# adc_wing.net
KiCad netlist of a schematic drawn in Altium Designer
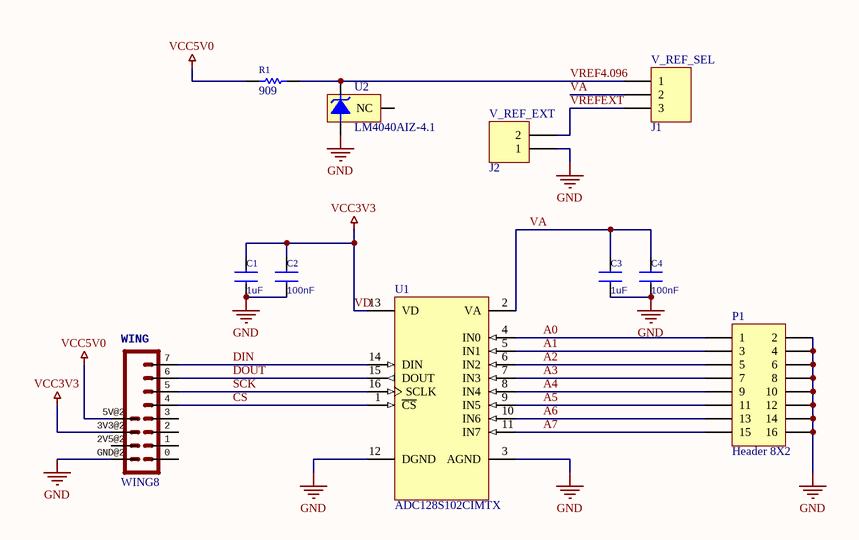
[diagram p0: adc_wing.SchDoc]

(export (version "E")
  (design (tool "Eeschema 10.0.6"))
  (components
    (comp (ref "C1")
      (value "1uF")
      (footprint "C0805")
      (description "Ceramic Capactor size 0805")
      (libsource (lib "MH - RCLDSX") (part "C0805"))
    )
    (comp (ref "C2")
      (value "100nF")
      (footprint "C0603")
      (description "Ceramic Capactor size 0603")
      (libsource (lib "MH - RCLDSX") (part "C0603"))
    )
    (comp (ref "C3")
      (value "1uF")
      (footprint "C0805")
      (description "Ceramic Capactor size 0805")
      (libsource (lib "MH - RCLDSX") (part "C0805"))
    )
    (comp (ref "C4")
      (value "100nF")
      (footprint "C0603")
      (description "Ceramic Capactor size 0603")
      (libsource (lib "MH - RCLDSX") (part "C0603"))
    )
    (comp (ref "J1")
      (value "V_REF_SEL")
      (footprint "PLS-3-3D")
      (description "Header, 3-Pin")
      (fields (field (name "PUBLISHER") "Altium Limited"))
      (libsource (lib "MH - Connectors") (part "PLS-3"))
    )
    (comp (ref "J2")
      (value "V_REF_EXT")
      (footprint "PLS-2-3D")
      (description "Header, 2-Pin")
      (fields (field (name "PUBLISHER") "Altium Limited"))
      (libsource (lib "MH - Connectors") (part "PLS-2"))
    )
    (comp (ref "P1")
      (value "Header 8X2")
      (footprint "HDR2X8")
      (description "Header, 8-Pin, Dual row")
      (fields (field (name "PUBLISHER") "Altium Limited"))
      (libsource (lib "Miscellaneous Connectors") (part "Header 8X2"))
    )
    (comp (ref "R1")
      (value "909")
      (footprint "R0805")
      (description "Chip Resistor size 0805")
      (libsource (lib "MH - RCLDSX") (part "R0805"))
    )
    (comp (ref "U1")
      (value "ADC128S102CIMTX")
      (footprint "MTC16_N")
      (description "8-Channel, 50 kSPS to 200 kSPS, 12-Bit A/D Converter, 16-pin TSSOP")
      (fields
        (field (name "PARTNUMBER") "ADC128S022CIMTX")
        (field (name "MANUFACTURER") "National Semiconductor")
      )
      (libsource (lib "National Semiconductor ADC") (part "ADC128S022CIMTX"))
    )
    (comp (ref "U2")
      (value "LM4040AIZ-4.1")
      (footprint "Z03A")
      (description "Precision Micropower Shunt Voltage Reference, 3-pin TO-92")
      (fields
        (field (name "MANUFACTURER") "National Semiconductor")
        (field (name "PUBLISHER") "Altium Limited")
      )
      (libsource (lib "NSC Voltage Reference") (part "LM4040AIZ-4.1"))
    )
    (comp (ref "WING") (value "WING8") (footprint "WINGSIDE_8BIT") (libsource (lib "Papilio") (part "WING8")))
  )
  (nets
    (net (code "1") (name "/A0") (class "Default")
      (node (ref "P1") (pin "1") (pinfunction "1_1") (pintype "passive"))
      (node (ref "U1") (pin "4") (pinfunction "IN0_4") (pintype "input"))
    )
    (net (code "2") (name "/A1") (class "Default")
      (node (ref "P1") (pin "3") (pinfunction "3_3") (pintype "passive"))
      (node (ref "U1") (pin "5") (pinfunction "IN1_5") (pintype "input"))
    )
    (net (code "3") (name "/A2") (class "Default")
      (node (ref "P1") (pin "5") (pinfunction "5_5") (pintype "passive"))
      (node (ref "U1") (pin "6") (pinfunction "IN2_6") (pintype "input"))
    )
    (net (code "4") (name "/A3") (class "Default")
      (node (ref "P1") (pin "7") (pinfunction "7_7") (pintype "passive"))
      (node (ref "U1") (pin "7") (pinfunction "IN3_7") (pintype "input"))
    )
    (net (code "5") (name "/A4") (class "Default")
      (node (ref "P1") (pin "9") (pinfunction "9_9") (pintype "passive"))
      (node (ref "U1") (pin "8") (pinfunction "IN4_8") (pintype "input"))
    )
    (net (code "6") (name "/A5") (class "Default")
      (node (ref "P1") (pin "11") (pinfunction "11_11") (pintype "passive"))
      (node (ref "U1") (pin "9") (pinfunction "IN5_9") (pintype "input"))
    )
    (net (code "7") (name "/A6") (class "Default")
      (node (ref "P1") (pin "13") (pinfunction "13_13") (pintype "passive"))
      (node (ref "U1") (pin "10") (pinfunction "IN6_10") (pintype "input"))
    )
    (net (code "8") (name "/A7") (class "Default")
      (node (ref "P1") (pin "15") (pinfunction "15_15") (pintype "passive"))
      (node (ref "U1") (pin "11") (pinfunction "IN7_11") (pintype "input"))
    )
    (net (code "9") (name "/CS") (class "Default")
      (node (ref "U1") (pin "1") (pinfunction "~{CS}_1") (pintype "input"))
      (node (ref "WING") (pin "4") (pinfunction "5_4") (pintype "passive"))
    )
    (net (code "10") (name "/DIN") (class "Default")
      (node (ref "U1") (pin "14") (pinfunction "DIN_14") (pintype "input"))
      (node (ref "WING") (pin "7") (pinfunction "8_7") (pintype "passive"))
    )
    (net (code "11") (name "/DOUT") (class "Default")
      (node (ref "U1") (pin "15") (pinfunction "DOUT_15") (pintype "output"))
      (node (ref "WING") (pin "6") (pinfunction "7_6") (pintype "passive"))
    )
    (net (code "12") (name "/SCK") (class "Default")
      (node (ref "U1") (pin "16") (pinfunction "SCLK_16") (pintype "input"))
      (node (ref "WING") (pin "5") (pinfunction "6_5") (pintype "passive"))
    )
    (net (code "13") (name "/VA") (class "Default")
      (node (ref "C3") (pin "2") (pintype "passive"))
      (node (ref "C4") (pin "2") (pintype "passive"))
      (node (ref "J1") (pin "2") (pinfunction "2_2") (pintype "passive"))
      (node (ref "U1") (pin "2") (pinfunction "VA_2") (pintype "power_in"))
    )
    (net (code "14") (name "/VREF4.096") (class "Default")
      (node (ref "J1") (pin "1") (pinfunction "1_1") (pintype "passive"))
      (node (ref "R1") (pin "2") (pinfunction "2_2") (pintype "passive"))
      (node (ref "U2") (pin "2") (pinfunction "+V_2") (pintype "passive"))
    )
    (net (code "15") (name "/VREFEXT") (class "Default")
      (node (ref "J1") (pin "3") (pinfunction "3_3") (pintype "passive"))
      (node (ref "J2") (pin "2") (pinfunction "2_2") (pintype "passive"))
    )
    (net (code "16") (name "GND") (class "Default")
      (node (ref "C1") (pin "1") (pintype "passive"))
      (node (ref "C2") (pin "1") (pintype "passive"))
      (node (ref "C3") (pin "1") (pintype "passive"))
      (node (ref "C4") (pin "1") (pintype "passive"))
      (node (ref "J2") (pin "1") (pinfunction "1_1") (pintype "passive"))
      (node (ref "P1") (pin "10") (pinfunction "10_10") (pintype "passive"))
      (node (ref "P1") (pin "12") (pinfunction "12_12") (pintype "passive"))
      (node (ref "P1") (pin "14") (pinfunction "14_14") (pintype "passive"))
      (node (ref "P1") (pin "16") (pinfunction "16_16") (pintype "passive"))
      (node (ref "P1") (pin "2") (pinfunction "2_2") (pintype "passive"))
      (node (ref "P1") (pin "4") (pinfunction "4_4") (pintype "passive"))
      (node (ref "P1") (pin "6") (pinfunction "6_6") (pintype "passive"))
      (node (ref "P1") (pin "8") (pinfunction "8_8") (pintype "passive"))
      (node (ref "U1") (pin "12") (pinfunction "DGND_12") (pintype "power_in"))
      (node (ref "U1") (pin "3") (pinfunction "AGND_3") (pintype "power_in"))
      (node (ref "U2") (pin "3") (pinfunction "-V_3") (pintype "passive"))
      (node (ref "WING") (pin "GND@2") (pinfunction "GND_GND@2") (pintype "passive"))
    )
    (net (code "17") (name "VCC3V3") (class "Default")
      (node (ref "C1") (pin "2") (pintype "passive"))
      (node (ref "C2") (pin "2") (pintype "passive"))
      (node (ref "U1") (pin "13") (pinfunction "VD_13") (pintype "power_in"))
      (node (ref "WING") (pin "3V3@2") (pinfunction "3V3_3V3@2") (pintype "passive"))
    )
    (net (code "18") (name "VCC5V0") (class "Default")
      (node (ref "R1") (pin "1") (pinfunction "1_1") (pintype "passive"))
      (node (ref "WING") (pin "5V@2") (pinfunction "5V_5V@2") (pintype "passive"))
    )
    (net (code "19") (name "unconnected-(U2-NC-Pad1)") (class "Default")
      (node (ref "U2") (pin "1") (pinfunction "NC_1") (pintype "passive"))
    )
    (net (code "20") (name "unconnected-(WING-1-Pad0)") (class "Default")
      (node (ref "WING") (pin "0") (pinfunction "1_0") (pintype "passive"))
    )
    (net (code "21") (name "unconnected-(WING-2-Pad1)") (class "Default")
      (node (ref "WING") (pin "1") (pinfunction "2_1") (pintype "passive"))
    )
    (net (code "22") (name "unconnected-(WING-2V5-Pad2V5@2)") (class "Default")
      (node (ref "WING") (pin "2V5@2") (pinfunction "2V5_2V5@2") (pintype "passive"))
    )
    (net (code "23") (name "unconnected-(WING-3-Pad2)") (class "Default")
      (node (ref "WING") (pin "2") (pinfunction "3_2") (pintype "passive"))
    )
    (net (code "24") (name "unconnected-(WING-4-Pad3)") (class "Default")
      (node (ref "WING") (pin "3") (pinfunction "4_3") (pintype "passive"))
    )
  )
)
